# Power.net
KiCad netlist of a schematic drawn in Altium Designer
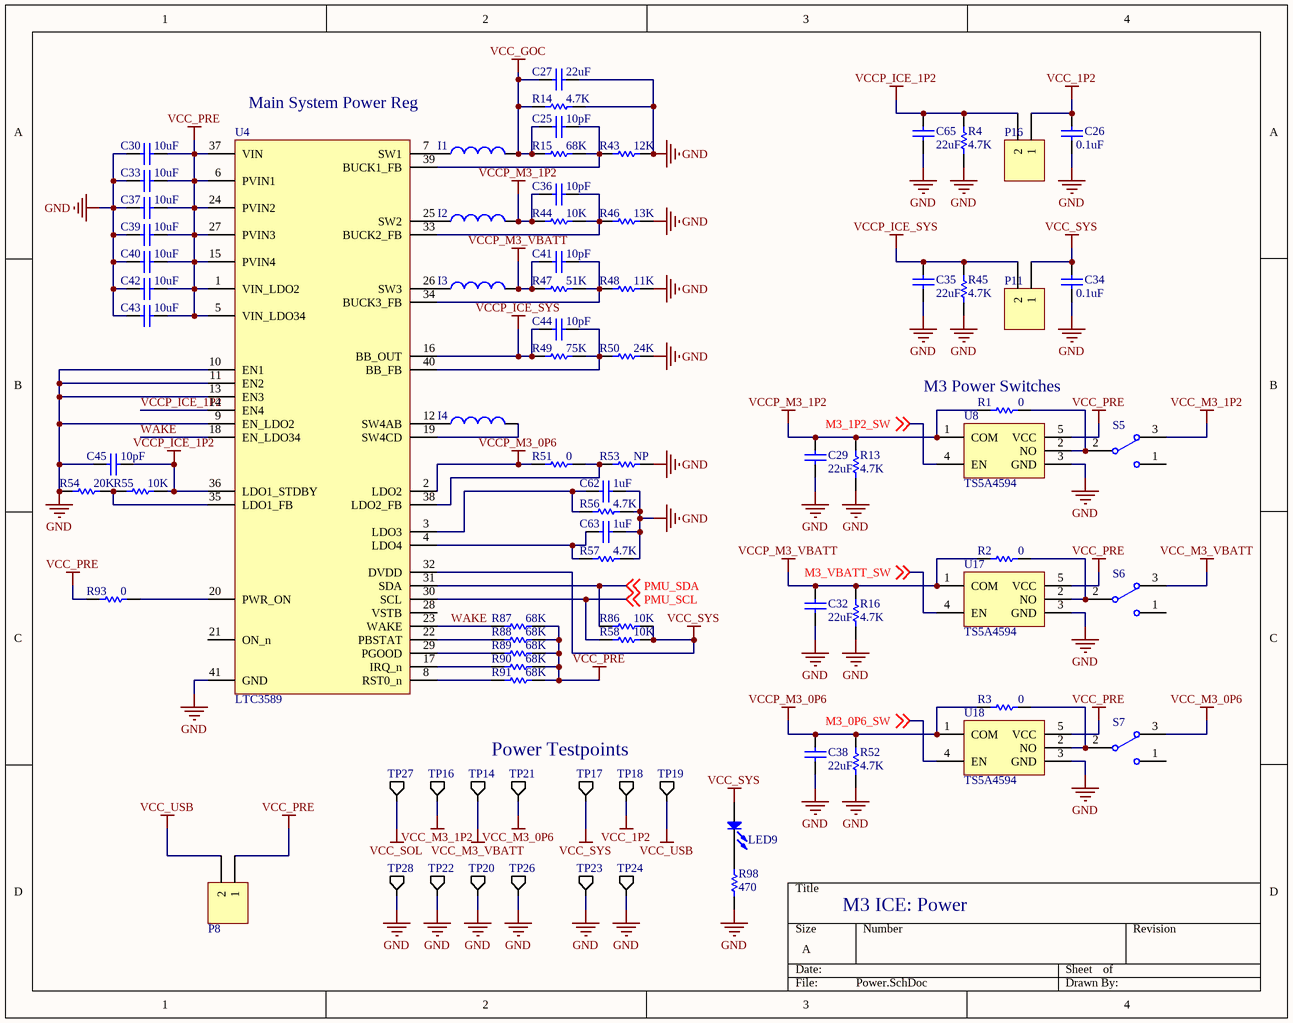
[diagram p0: Power.SchDoc]

(export (version "E")
  (design (tool "Eeschema 10.0.6"))
  (components
    (comp (ref "C25")
      (value "10pF")
      (footprint "0402")
      (description "Capacitor (Semiconductor SIM Model)")
      (fields
        (field (name "DISTPARTNO") "445-1235-1-ND")
        (field (name "MANPARTNO") "C1005C0G1H100D")
        (field (name "PUBLISHER") "Altium Limited")
      )
      (libsource (lib "Miscellaneous Devices") (part "Cap Semi"))
    )
    (comp (ref "C26")
      (value "0.1uF")
      (footprint "1608[0603]")
      (description "Capacitor (Semiconductor SIM Model)")
      (fields
        (field (name "DISTPARTNO") "445-1317-1-ND")
        (field (name "MANPARTNO") "C1608X7R1C104K")
        (field (name "PUBLISHER") "Altium Limited")
      )
      (libsource (lib "Miscellaneous Devices") (part "Cap Semi"))
    )
    (comp (ref "C27")
      (value "22uF")
      (footprint "0805")
      (description "Capacitor (Semiconductor SIM Model)")
      (fields
        (field (name "DISTPARTNO") "587-2782-1-ND")
        (field (name "MANPARTNO") "LMK316AB7226ML-TR")
        (field (name "PUBLISHER") "Altium Limited")
      )
      (libsource (lib "M3") (part "Cap Chip"))
    )
    (comp (ref "C29")
      (value "22uF")
      (footprint "0805")
      (description "Capacitor (Semiconductor SIM Model)")
      (fields
        (field (name "DISTPARTNO") "587-2782-1-ND")
        (field (name "MANPARTNO") "LMK316AB7226ML-TR")
        (field (name "PUBLISHER") "Altium Limited")
      )
      (libsource (lib "M3") (part "Cap Chip"))
    )
    (comp (ref "C30")
      (value "10uF")
      (footprint "0805")
      (description "Capacitor (Semiconductor SIM Model)")
      (fields
        (field (name "DISTPARTNO") "445-6857-1-ND")
        (field (name "MANPARTNO") "C2012X7R1A106K")
        (field (name "PUBLISHER") "Altium Limited")
      )
      (libsource (lib "M3") (part "Cap Chip"))
    )
    (comp (ref "C32")
      (value "22uF")
      (footprint "0805")
      (description "Capacitor (Semiconductor SIM Model)")
      (fields
        (field (name "DISTPARTNO") "587-2782-1-ND")
        (field (name "MANPARTNO") "LMK316AB7226ML-TR")
        (field (name "PUBLISHER") "Altium Limited")
      )
      (libsource (lib "M3") (part "Cap Chip"))
    )
    (comp (ref "C33")
      (value "10uF")
      (footprint "0805")
      (description "Capacitor (Semiconductor SIM Model)")
      (fields
        (field (name "DISTPARTNO") "445-6857-1-ND")
        (field (name "MANPARTNO") "C2012X7R1A106K")
        (field (name "PUBLISHER") "Altium Limited")
      )
      (libsource (lib "M3") (part "Cap Chip"))
    )
    (comp (ref "C34")
      (value "0.1uF")
      (footprint "1608[0603]")
      (description "Capacitor (Semiconductor SIM Model)")
      (fields
        (field (name "DISTPARTNO") "445-1317-1-ND")
        (field (name "MANPARTNO") "C1608X7R1C104K")
        (field (name "PUBLISHER") "Altium Limited")
      )
      (libsource (lib "Miscellaneous Devices") (part "Cap Semi"))
    )
    (comp (ref "C35")
      (value "22uF")
      (footprint "0805")
      (description "Capacitor (Semiconductor SIM Model)")
      (fields
        (field (name "DISTPARTNO") "587-2782-1-ND")
        (field (name "MANPARTNO") "LMK316AB7226ML-TR")
        (field (name "PUBLISHER") "Altium Limited")
      )
      (libsource (lib "M3") (part "Cap Chip"))
    )
    (comp (ref "C36")
      (value "10pF")
      (footprint "0402")
      (description "Capacitor (Semiconductor SIM Model)")
      (fields
        (field (name "DISTPARTNO") "445-1235-1-ND")
        (field (name "MANPARTNO") "C1005C0G1H100D")
        (field (name "PUBLISHER") "Altium Limited")
      )
      (libsource (lib "Miscellaneous Devices") (part "Cap Semi"))
    )
    (comp (ref "C37")
      (value "10uF")
      (footprint "0805")
      (description "Capacitor (Semiconductor SIM Model)")
      (fields
        (field (name "DISTPARTNO") "445-6857-1-ND")
        (field (name "MANPARTNO") "C2012X7R1A106K")
        (field (name "PUBLISHER") "Altium Limited")
      )
      (libsource (lib "M3") (part "Cap Chip"))
    )
    (comp (ref "C38")
      (value "22uF")
      (footprint "0805")
      (description "Capacitor (Semiconductor SIM Model)")
      (fields
        (field (name "DISTPARTNO") "587-2782-1-ND")
        (field (name "MANPARTNO") "LMK316AB7226ML-TR")
        (field (name "PUBLISHER") "Altium Limited")
      )
      (libsource (lib "M3") (part "Cap Chip"))
    )
    (comp (ref "C39")
      (value "10uF")
      (footprint "0805")
      (description "Capacitor (Semiconductor SIM Model)")
      (fields
        (field (name "DISTPARTNO") "445-6857-1-ND")
        (field (name "MANPARTNO") "C2012X7R1A106K")
        (field (name "PUBLISHER") "Altium Limited")
      )
      (libsource (lib "M3") (part "Cap Chip"))
    )
    (comp (ref "C40")
      (value "10uF")
      (footprint "0805")
      (description "Capacitor (Semiconductor SIM Model)")
      (fields
        (field (name "DISTPARTNO") "445-6857-1-ND")
        (field (name "MANPARTNO") "C2012X7R1A106K")
        (field (name "PUBLISHER") "Altium Limited")
      )
      (libsource (lib "M3") (part "Cap Chip"))
    )
    (comp (ref "C41")
      (value "10pF")
      (footprint "0402")
      (description "Capacitor (Semiconductor SIM Model)")
      (fields
        (field (name "DISTPARTNO") "445-1235-1-ND")
        (field (name "MANPARTNO") "C1005C0G1H100D")
        (field (name "PUBLISHER") "Altium Limited")
      )
      (libsource (lib "Miscellaneous Devices") (part "Cap Semi"))
    )
    (comp (ref "C42")
      (value "10uF")
      (footprint "0805")
      (description "Capacitor (Semiconductor SIM Model)")
      (fields
        (field (name "DISTPARTNO") "445-6857-1-ND")
        (field (name "MANPARTNO") "C2012X7R1A106K")
        (field (name "PUBLISHER") "Altium Limited")
      )
      (libsource (lib "M3") (part "Cap Chip"))
    )
    (comp (ref "C43")
      (value "10uF")
      (footprint "0805")
      (description "Capacitor (Semiconductor SIM Model)")
      (fields
        (field (name "DISTPARTNO") "445-6857-1-ND")
        (field (name "MANPARTNO") "C2012X7R1A106K")
        (field (name "PUBLISHER") "Altium Limited")
      )
      (libsource (lib "M3") (part "Cap Chip"))
    )
    (comp (ref "C44")
      (value "10pF")
      (footprint "0402")
      (description "Capacitor (Semiconductor SIM Model)")
      (fields
        (field (name "DISTPARTNO") "445-1235-1-ND")
        (field (name "MANPARTNO") "C1005C0G1H100D")
        (field (name "PUBLISHER") "Altium Limited")
      )
      (libsource (lib "Miscellaneous Devices") (part "Cap Semi"))
    )
    (comp (ref "C45")
      (value "10pF")
      (footprint "0402")
      (description "Capacitor (Semiconductor SIM Model)")
      (fields
        (field (name "DISTPARTNO") "445-1235-1-ND")
        (field (name "MANPARTNO") "C1005C0G1H100D")
        (field (name "PUBLISHER") "Altium Limited")
      )
      (libsource (lib "Miscellaneous Devices") (part "Cap Semi"))
    )
    (comp (ref "C62")
      (value "1uF")
      (footprint "0402")
      (description "Capacitor (Semiconductor SIM Model)")
      (fields
        (field (name "DISTPARTNO") "445-4991-1-ND")
        (field (name "MANPARTNO") "C1005X5R1A105M")
        (field (name "PUBLISHER") "Altium Limited")
      )
      (libsource (lib "Miscellaneous Devices") (part "Cap Semi"))
    )
    (comp (ref "C63")
      (value "1uF")
      (footprint "0402")
      (description "Capacitor (Semiconductor SIM Model)")
      (fields
        (field (name "DISTPARTNO") "445-4991-1-ND")
        (field (name "MANPARTNO") "C1005X5R1A105M")
        (field (name "PUBLISHER") "Altium Limited")
      )
      (libsource (lib "Miscellaneous Devices") (part "Cap Semi"))
    )
    (comp (ref "C65")
      (value "22uF")
      (footprint "0805")
      (description "Capacitor (Semiconductor SIM Model)")
      (fields
        (field (name "DISTPARTNO") "587-2782-1-ND")
        (field (name "MANPARTNO") "LMK316AB7226ML-TR")
        (field (name "PUBLISHER") "Altium Limited")
      )
      (libsource (lib "M3") (part "Cap Chip"))
    )
    (comp (ref "I1")
      (value "NR5040T1R5N")
      (footprint "INDUCTOR_.118x.142mm")
      (fields (field (name "DISTPARTNO") "541-1327-1-ND") (field (name "MANPARTNO") "IHLP1212AEER1R0M11"))
      (libsource (lib "M3") (part "IHLP1212"))
    )
    (comp (ref "I2")
      (value "NR5040T1R5N")
      (footprint "INDUCTOR_.118x.142mm")
      (fields (field (name "DISTPARTNO") "541-1327-1-ND") (field (name "MANPARTNO") "IHLP1212AEER1R0M11"))
      (libsource (lib "M3") (part "IHLP1212"))
    )
    (comp (ref "I3")
      (value "NR5040T1R5N")
      (footprint "INDUCTOR_.118x.142mm")
      (fields (field (name "DISTPARTNO") "541-1327-1-ND") (field (name "MANPARTNO") "IHLP1212AEER1R0M11"))
      (libsource (lib "M3") (part "IHLP1212"))
    )
    (comp (ref "I4")
      (value "NR5040T1R5N")
      (footprint "INDUCTOR_.118x.142mm")
      (fields (field (name "DISTPARTNO") "541-1327-1-ND") (field (name "MANPARTNO") "IHLP1212AEER1R0M11"))
      (libsource (lib "M3") (part "IHLP1212"))
    )
    (comp (ref "LED9")
      (value "LED 1206")
      (footprint "1206_LED")
      (fields (field (name "DISTPARTNO") "160-1169-1-ND") (field (name "MANPARTNO") "LTST-C150GKT"))
      (libsource (lib "M3") (part "LED 1206"))
    )
    (comp (ref "P8")
      (value "Header 2")
      (footprint "HDR1X2")
      (description "Header, 2-Pin")
      (fields (field (name "PUBLISHER") "Altium Limited"))
      (libsource (lib "Miscellaneous Connectors") (part "Header 2"))
    )
    (comp (ref "P11")
      (value "Header 2")
      (footprint "HDR1X2")
      (description "Header, 2-Pin")
      (fields (field (name "PUBLISHER") "Altium Limited"))
      (libsource (lib "Miscellaneous Connectors") (part "Header 2"))
    )
    (comp (ref "P16")
      (value "Header 2")
      (footprint "HDR1X2")
      (description "Header, 2-Pin")
      (fields (field (name "PUBLISHER") "Altium Limited"))
      (libsource (lib "Miscellaneous Connectors") (part "Header 2"))
    )
    (comp (ref "R1")
      (value "0")
      (footprint "0603")
      (description "Semiconductor Resistor")
      (fields
        (field (name "DISTPARTNO") "P0.0GCT-ND")
        (field (name "MANPARTNO") "ERJ-3GEY0R00V")
        (field (name "PUBLISHER") "Altium Limited")
      )
      (libsource (lib "M3") (part "Res Chip"))
    )
    (comp (ref "R2")
      (value "0")
      (footprint "0603")
      (description "Semiconductor Resistor")
      (fields
        (field (name "DISTPARTNO") "P0.0GCT-ND")
        (field (name "MANPARTNO") "ERJ-3GEY0R00V")
        (field (name "PUBLISHER") "Altium Limited")
      )
      (libsource (lib "M3") (part "Res Chip"))
    )
    (comp (ref "R3")
      (value "0")
      (footprint "0603")
      (description "Semiconductor Resistor")
      (fields
        (field (name "DISTPARTNO") "P0.0GCT-ND")
        (field (name "MANPARTNO") "ERJ-3GEY0R00V")
        (field (name "PUBLISHER") "Altium Limited")
      )
      (libsource (lib "M3") (part "Res Chip"))
    )
    (comp (ref "R4")
      (value "4.7K")
      (footprint "0603")
      (description "Semiconductor Resistor")
      (fields
        (field (name "DISTPARTNO") "P4.7KGCT-ND")
        (field (name "MANPARTNO") "ERJ-3GEYJ472V")
        (field (name "PUBLISHER") "Altium Limited")
      )
      (libsource (lib "M3") (part "Res Chip"))
    )
    (comp (ref "R13")
      (value "4.7K")
      (footprint "0603")
      (description "Semiconductor Resistor")
      (fields
        (field (name "DISTPARTNO") "P4.7KGCT-ND")
        (field (name "MANPARTNO") "ERJ-3GEYJ472V")
        (field (name "PUBLISHER") "Altium Limited")
      )
      (libsource (lib "M3") (part "Res Chip"))
    )
    (comp (ref "R14")
      (value "4.7K")
      (footprint "0603")
      (description "Semiconductor Resistor")
      (fields
        (field (name "DISTPARTNO") "P4.7KGCT-ND")
        (field (name "MANPARTNO") "ERJ-3GEYJ472V")
        (field (name "PUBLISHER") "Altium Limited")
      )
      (libsource (lib "M3") (part "Res Chip"))
    )
    (comp (ref "R15")
      (value "68K")
      (footprint "0402")
      (description "Semiconductor Resistor")
      (fields
        (field (name "DISTPARTNO") "P68.0KLCT-ND")
        (field (name "MANPARTNO") "ERJ-2RKF6802X")
        (field (name "PUBLISHER") "Altium Limited")
      )
      (libsource (lib "M3") (part "Res Chip"))
    )
    (comp (ref "R16")
      (value "4.7K")
      (footprint "0603")
      (description "Semiconductor Resistor")
      (fields
        (field (name "DISTPARTNO") "P4.7KGCT-ND")
        (field (name "MANPARTNO") "ERJ-3GEYJ472V")
        (field (name "PUBLISHER") "Altium Limited")
      )
      (libsource (lib "M3") (part "Res Chip"))
    )
    (comp (ref "R43")
      (value "12K")
      (footprint "0402")
      (description "Semiconductor Resistor")
      (fields
        (field (name "DISTPARTNO") "P12.0KLCT-ND")
        (field (name "MANPARTNO") "ERJ-2RKF1202X")
        (field (name "PUBLISHER") "Altium Limited")
      )
      (libsource (lib "M3") (part "Res Chip"))
    )
    (comp (ref "R44")
      (value "10K")
      (footprint "0402")
      (description "Semiconductor Resistor")
      (fields
        (field (name "DISTPARTNO") "P10.0KLCT-ND")
        (field (name "MANPARTNO") "ERJ-2RKF1002X")
        (field (name "PUBLISHER") "Altium Limited")
      )
      (libsource (lib "M3") (part "Res Chip"))
    )
    (comp (ref "R45")
      (value "4.7K")
      (footprint "0603")
      (description "Semiconductor Resistor")
      (fields
        (field (name "DISTPARTNO") "P4.7KGCT-ND")
        (field (name "MANPARTNO") "ERJ-3GEYJ472V")
        (field (name "PUBLISHER") "Altium Limited")
      )
      (libsource (lib "M3") (part "Res Chip"))
    )
    (comp (ref "R46")
      (value "13K")
      (footprint "0402")
      (description "Semiconductor Resistor")
      (fields
        (field (name "DISTPARTNO") "311-13.0KLRCT-ND")
        (field (name "MANPARTNO") "RC0402FR-0713KL")
        (field (name "PUBLISHER") "Altium Limited")
      )
      (libsource (lib "M3") (part "Res Chip"))
    )
    (comp (ref "R47")
      (value "51K")
      (footprint "0402")
      (description "Semiconductor Resistor")
      (fields
        (field (name "DISTPARTNO") "P51.0KLCT-ND")
        (field (name "MANPARTNO") "ERJ-2RKF5102X")
        (field (name "PUBLISHER") "Altium Limited")
      )
      (libsource (lib "M3") (part "Res Chip"))
    )
    (comp (ref "R48")
      (value "11K")
      (footprint "0402")
      (description "Semiconductor Resistor")
      (fields
        (field (name "DISTPARTNO") "P11.0KLCT-ND")
        (field (name "MANPARTNO") "ERJ-2RKF1102X")
        (field (name "PUBLISHER") "Altium Limited")
      )
      (libsource (lib "M3") (part "Res Chip"))
    )
    (comp (ref "R49")
      (value "75K")
      (footprint "0402")
      (description "Semiconductor Resistor")
      (fields
        (field (name "DISTPARTNO") "P75.0KLCT-ND")
        (field (name "MANPARTNO") "ERJ-2RKF7502X")
        (field (name "PUBLISHER") "Altium Limited")
      )
      (libsource (lib "M3") (part "Res Chip"))
    )
    (comp (ref "R50")
      (value "24K")
      (footprint "0402")
      (description "Semiconductor Resistor")
      (fields
        (field (name "DISTPARTNO") "RMCF0402FT24K0CT-ND")
        (field (name "MANPARTNO") "RMCF0402FT24K0")
        (field (name "PUBLISHER") "Altium Limited")
      )
      (libsource (lib "M3") (part "Res Chip"))
    )
    (comp (ref "R51")
      (value "0")
      (footprint "0402")
      (description "Semiconductor Resistor")
      (fields
        (field (name "DISTPARTNO") "P0.0JCT-ND")
        (field (name "MANPARTNO") "ERJ-2GE0R00X")
        (field (name "PUBLISHER") "Altium Limited")
      )
      (libsource (lib "M3") (part "Res Chip"))
    )
    (comp (ref "R52")
      (value "4.7K")
      (footprint "0603")
      (description "Semiconductor Resistor")
      (fields
        (field (name "DISTPARTNO") "P4.7KGCT-ND")
        (field (name "MANPARTNO") "ERJ-3GEYJ472V")
        (field (name "PUBLISHER") "Altium Limited")
      )
      (libsource (lib "M3") (part "Res Chip"))
    )
    (comp (ref "R53")
      (value "NP")
      (footprint "0402")
      (description "Semiconductor Resistor")
      (fields (field (name "Comment") "Res Chip") (field (name "PUBLISHER") "Altium Limited"))
      (libsource (lib "M3") (part "Res Chip"))
    )
    (comp (ref "R54")
      (value "20K")
      (footprint "0402")
      (description "Semiconductor Resistor")
      (fields
        (field (name "DISTPARTNO") "P20.0KLCT-ND")
        (field (name "MANPARTNO") "ERJ-2RKF2002X")
        (field (name "PUBLISHER") "Altium Limited")
      )
      (libsource (lib "M3") (part "Res Chip"))
    )
    (comp (ref "R55")
      (value "10K")
      (footprint "0402")
      (description "Semiconductor Resistor")
      (fields
        (field (name "DISTPARTNO") "P10.0KLCT-ND")
        (field (name "MANPARTNO") "ERJ-2RKF1002X")
        (field (name "PUBLISHER") "Altium Limited")
      )
      (libsource (lib "M3") (part "Res Chip"))
    )
    (comp (ref "R56")
      (value "4.7K")
      (footprint "0402")
      (description "Semiconductor Resistor")
      (fields
        (field (name "DISTPARTNO") "P4.70KLCT-ND")
        (field (name "MANPARTNO") "ERJ-2RKF4701X")
        (field (name "PUBLISHER") "Altium Limited")
      )
      (libsource (lib "M3") (part "Res Chip"))
    )
    (comp (ref "R57")
      (value "4.7K")
      (footprint "0402")
      (description "Semiconductor Resistor")
      (fields
        (field (name "DISTPARTNO") "P4.70KLCT-ND")
        (field (name "MANPARTNO") "ERJ-2RKF4701X")
        (field (name "PUBLISHER") "Altium Limited")
      )
      (libsource (lib "M3") (part "Res Chip"))
    )
    (comp (ref "R58")
      (value "10K")
      (footprint "0402")
      (description "Semiconductor Resistor")
      (fields
        (field (name "DISTPARTNO") "P10.0KLCT-ND")
        (field (name "MANPARTNO") "ERJ-2RKF1002X")
        (field (name "PUBLISHER") "Altium Limited")
      )
      (libsource (lib "M3") (part "Res Chip"))
    )
    (comp (ref "R86")
      (value "10K")
      (footprint "0402")
      (description "Semiconductor Resistor")
      (fields
        (field (name "DISTPARTNO") "P10.0KLCT-ND")
        (field (name "MANPARTNO") "ERJ-2RKF1002X")
        (field (name "PUBLISHER") "Altium Limited")
      )
      (libsource (lib "M3") (part "Res Chip"))
    )
    (comp (ref "R87")
      (value "68K")
      (footprint "0402")
      (description "Semiconductor Resistor")
      (fields
        (field (name "DISTPARTNO") "P68.0KLCT-ND")
        (field (name "MANPARTNO") "ERJ-2RKF6802X")
        (field (name "PUBLISHER") "Altium Limited")
      )
      (libsource (lib "M3") (part "Res Chip"))
    )
    (comp (ref "R88")
      (value "68K")
      (footprint "0402")
      (description "Semiconductor Resistor")
      (fields
        (field (name "DISTPARTNO") "P68.0KLCT-ND")
        (field (name "MANPARTNO") "ERJ-2RKF6802X")
        (field (name "PUBLISHER") "Altium Limited")
      )
      (libsource (lib "M3") (part "Res Chip"))
    )
    (comp (ref "R89")
      (value "68K")
      (footprint "0402")
      (description "Semiconductor Resistor")
      (fields
        (field (name "DISTPARTNO") "P68.0KLCT-ND")
        (field (name "MANPARTNO") "ERJ-2RKF6802X")
        (field (name "PUBLISHER") "Altium Limited")
      )
      (libsource (lib "M3") (part "Res Chip"))
    )
    (comp (ref "R90")
      (value "68K")
      (footprint "0402")
      (description "Semiconductor Resistor")
      (fields
        (field (name "DISTPARTNO") "P68.0KLCT-ND")
        (field (name "MANPARTNO") "ERJ-2RKF6802X")
        (field (name "PUBLISHER") "Altium Limited")
      )
      (libsource (lib "M3") (part "Res Chip"))
    )
    (comp (ref "R91")
      (value "68K")
      (footprint "0402")
      (description "Semiconductor Resistor")
      (fields
        (field (name "DISTPARTNO") "P68.0KLCT-ND")
        (field (name "MANPARTNO") "ERJ-2RKF6802X")
        (field (name "PUBLISHER") "Altium Limited")
      )
      (libsource (lib "M3") (part "Res Chip"))
    )
    (comp (ref "R93")
      (value "0")
      (footprint "0402")
      (description "Semiconductor Resistor")
      (fields
        (field (name "DISTPARTNO") "P0.0JCT-ND")
        (field (name "MANPARTNO") "ERJ-2GE0R00X")
        (field (name "PUBLISHER") "Altium Limited")
      )
      (libsource (lib "M3") (part "Res Chip"))
    )
    (comp (ref "R98")
      (value "470")
      (footprint "0603")
      (description "Semiconductor Resistor")
      (fields
        (field (name "DISTPARTNO") "P470GCT-ND")
        (field (name "MANPARTNO") "ERJ-3GEYJ471V")
        (field (name "PUBLISHER") "Altium Limited")
      )
      (libsource (lib "M3") (part "Res Chip"))
    )
    (comp (ref "S5")
      (value "OS102011MS2QN1")
      (footprint "SPDT_SW2")
      (description "SPDT Slide Switch")
      (fields (field (name "DISTPARTNO") "CKN9565-ND"))
      (libsource (lib "M3") (part "OS102011MS2QN1"))
    )
    (comp (ref "S6")
      (value "OS102011MS2QN1")
      (footprint "SPDT_SW2")
      (description "SPDT Slide Switch")
      (fields (field (name "DISTPARTNO") "CKN9565-ND"))
      (libsource (lib "M3") (part "OS102011MS2QN1"))
    )
    (comp (ref "S7")
      (value "OS102011MS2QN1")
      (footprint "SPDT_SW2")
      (description "SPDT Slide Switch")
      (fields (field (name "DISTPARTNO") "CKN9565-ND"))
      (libsource (lib "M3") (part "OS102011MS2QN1"))
    )
    (comp (ref "TP14") (value "TP") (footprint "TP") (libsource (lib "M3") (part "TP")))
    (comp (ref "TP16") (value "TP") (footprint "TP") (libsource (lib "M3") (part "TP")))
    (comp (ref "TP17") (value "TP") (footprint "TP") (libsource (lib "M3") (part "TP")))
    (comp (ref "TP18") (value "TP") (footprint "TP") (libsource (lib "M3") (part "TP")))
    (comp (ref "TP19") (value "TP") (footprint "TP") (libsource (lib "M3") (part "TP")))
    (comp (ref "TP20") (value "TP") (footprint "TP") (libsource (lib "M3") (part "TP")))
    (comp (ref "TP21") (value "TP") (footprint "TP") (libsource (lib "M3") (part "TP")))
    (comp (ref "TP22") (value "TP") (footprint "TP") (libsource (lib "M3") (part "TP")))
    (comp (ref "TP23") (value "TP") (footprint "TP") (libsource (lib "M3") (part "TP")))
    (comp (ref "TP24") (value "TP") (footprint "TP") (libsource (lib "M3") (part "TP")))
    (comp (ref "TP26") (value "TP") (footprint "TP") (libsource (lib "M3") (part "TP")))
    (comp (ref "TP27") (value "TP") (footprint "TP") (libsource (lib "M3") (part "TP")))
    (comp (ref "TP28") (value "TP") (footprint "TP") (libsource (lib "M3") (part "TP")))
    (comp (ref "U4")
      (value "LTC3589")
      (footprint "QFN-40")
      (fields (field (name "DISTPARTNO") "LTC3589EUJ-2#PBF-ND") (field (name "MANPARTNO") "LTC3589EUJ-2#PBF"))
      (libsource (lib "M3") (part "LTC3589"))
    )
    (comp (ref "U8")
      (value "TS5A4594")
      (footprint "SOT25")
      (description "SPST Analog Switch")
      (fields (field (name "DISTPARTNO") "296-17705-1-ND") (field (name "MANPARTNO") "TS5A4594DBVR"))
      (libsource (lib "M3") (part "TS5A4594"))
    )
    (comp (ref "U17")
      (value "TS5A4594")
      (footprint "SOT25")
      (description "SPST Analog Switch")
      (fields (field (name "DISTPARTNO") "296-17705-1-ND") (field (name "MANPARTNO") "TS5A4594DBVR"))
      (libsource (lib "M3") (part "TS5A4594"))
    )
    (comp (ref "U18")
      (value "TS5A4594")
      (footprint "SOT25")
      (description "SPST Analog Switch")
      (fields (field (name "DISTPARTNO") "296-17705-1-ND") (field (name "MANPARTNO") "TS5A4594DBVR"))
      (libsource (lib "M3") (part "TS5A4594"))
    )
  )
  (nets
    (net (code "1") (name "/WAKE") (class "Default")
      (node (ref "R87") (pin "1") (pinfunction "1_1") (pintype "passive"))
      (node (ref "U4") (pin "18") (pinfunction "EN_LDO34_18") (pintype "passive"))
      (node (ref "U4") (pin "23") (pinfunction "WAKE_23") (pintype "passive"))
    )
    (net (code "2") (name "GND") (class "Default")
      (node (ref "C26") (pin "1") (pinfunction "1_1") (pintype "passive"))
      (node (ref "C27") (pin "1") (pinfunction "1_1") (pintype "passive"))
      (node (ref "C29") (pin "1") (pinfunction "1_1") (pintype "passive"))
      (node (ref "C30") (pin "2") (pinfunction "2_2") (pintype "passive"))
      (node (ref "C32") (pin "1") (pinfunction "1_1") (pintype "passive"))
      (node (ref "C33") (pin "2") (pinfunction "2_2") (pintype "passive"))
      (node (ref "C34") (pin "1") (pinfunction "1_1") (pintype "passive"))
      (node (ref "C35") (pin "1") (pinfunction "1_1") (pintype "passive"))
      (node (ref "C37") (pin "2") (pinfunction "2_2") (pintype "passive"))
      (node (ref "C38") (pin "1") (pinfunction "1_1") (pintype "passive"))
      (node (ref "C39") (pin "2") (pinfunction "2_2") (pintype "passive"))
      (node (ref "C40") (pin "2") (pinfunction "2_2") (pintype "passive"))
      (node (ref "C42") (pin "2") (pinfunction "2_2") (pintype "passive"))
      (node (ref "C43") (pin "2") (pinfunction "2_2") (pintype "passive"))
      (node (ref "C45") (pin "2") (pinfunction "2_2") (pintype "passive"))
      (node (ref "C62") (pin "1") (pinfunction "1_1") (pintype "passive"))
      (node (ref "C63") (pin "1") (pinfunction "1_1") (pintype "passive"))
      (node (ref "C65") (pin "2") (pinfunction "2_2") (pintype "passive"))
      (node (ref "R13") (pin "1") (pinfunction "1_1") (pintype "passive"))
      (node (ref "R14") (pin "1") (pinfunction "1_1") (pintype "passive"))
      (node (ref "R16") (pin "1") (pinfunction "1_1") (pintype "passive"))
      (node (ref "R4") (pin "2") (pinfunction "2_2") (pintype "passive"))
      (node (ref "R43") (pin "2") (pinfunction "2_2") (pintype "passive"))
      (node (ref "R45") (pin "1") (pinfunction "1_1") (pintype "passive"))
      (node (ref "R46") (pin "2") (pinfunction "2_2") (pintype "passive"))
      (node (ref "R48") (pin "2") (pinfunction "2_2") (pintype "passive"))
      (node (ref "R50") (pin "2") (pinfunction "2_2") (pintype "passive"))
      (node (ref "R52") (pin "1") (pinfunction "1_1") (pintype "passive"))
      (node (ref "R53") (pin "2") (pinfunction "2_2") (pintype "passive"))
      (node (ref "R54") (pin "1") (pinfunction "1_1") (pintype "passive"))
      (node (ref "R56") (pin "2") (pinfunction "2_2") (pintype "passive"))
      (node (ref "R57") (pin "2") (pinfunction "2_2") (pintype "passive"))
      (node (ref "R98") (pin "1") (pinfunction "1_1") (pintype "passive"))
      (node (ref "TP20") (pin "1") (pinfunction "A_1") (pintype "passive"))
      (node (ref "TP22") (pin "1") (pinfunction "A_1") (pintype "passive"))
      (node (ref "TP23") (pin "1") (pinfunction "A_1") (pintype "passive"))
      (node (ref "TP24") (pin "1") (pinfunction "A_1") (pintype "passive"))
      (node (ref "TP26") (pin "1") (pinfunction "A_1") (pintype "passive"))
      (node (ref "TP28") (pin "1") (pinfunction "A_1") (pintype "passive"))
      (node (ref "U17") (pin "3") (pinfunction "GND_3") (pintype "passive"))
      (node (ref "U18") (pin "3") (pinfunction "GND_3") (pintype "passive"))
      (node (ref "U4") (pin "10") (pinfunction "EN1_10") (pintype "passive"))
      (node (ref "U4") (pin "11") (pinfunction "EN2_11") (pintype "passive"))
      (node (ref "U4") (pin "13") (pinfunction "EN3_13") (pintype "passive"))
      (node (ref "U4") (pin "41") (pinfunction "GND_41") (pintype "passive"))
      (node (ref "U4") (pin "9") (pinfunction "EN_LDO2_9") (pintype "passive"))
      (node (ref "U8") (pin "3") (pinfunction "GND_3") (pintype "passive"))
    )
    (net (code "3") (name "M3_0P6_SW") (class "Default")
      (node (ref "U18") (pin "4") (pinfunction "EN_4") (pintype "passive"))
    )
    (net (code "4") (name "M3_1P2_SW") (class "Default")
      (node (ref "U8") (pin "4") (pinfunction "EN_4") (pintype "passive"))
    )
    (net (code "5") (name "M3_VBATT_SW") (class "Default")
      (node (ref "U17") (pin "4") (pinfunction "EN_4") (pintype "passive"))
    )
    (net (code "6") (name "Net-(LED9-K)") (class "Default")
      (node (ref "LED9") (pin "2") (pinfunction "K_2") (pintype "passive"))
      (node (ref "R98") (pin "2") (pinfunction "2_2") (pintype "passive"))
    )
    (net (code "7") (name "Net-(U4-BB_FB)") (class "Default")
      (node (ref "C44") (pin "1") (pinfunction "1_1") (pintype "passive"))
      (node (ref "R49") (pin "2") (pinfunction "2_2") (pintype "passive"))
      (node (ref "R50") (pin "1") (pinfunction "1_1") (pintype "passive"))
      (node (ref "U4") (pin "40") (pinfunction "BB_FB_40") (pintype "passive"))
    )
    (net (code "8") (name "Net-(U4-BUCK1_FB)") (class "Default")
      (node (ref "C25") (pin "1") (pinfunction "1_1") (pintype "passive"))
      (node (ref "R15") (pin "2") (pinfunction "2_2") (pintype "passive"))
      (node (ref "R43") (pin "1") (pinfunction "1_1") (pintype "passive"))
      (node (ref "U4") (pin "39") (pinfunction "BUCK1_FB_39") (pintype "passive"))
    )
    (net (code "9") (name "Net-(U4-BUCK2_FB)") (class "Default")
      (node (ref "C36") (pin "1") (pinfunction "1_1") (pintype "passive"))
      (node (ref "R44") (pin "2") (pinfunction "2_2") (pintype "passive"))
      (node (ref "R46") (pin "1") (pinfunction "1_1") (pintype "passive"))
      (node (ref "U4") (pin "33") (pinfunction "BUCK2_FB_33") (pintype "passive"))
    )
    (net (code "10") (name "Net-(U4-BUCK3_FB)") (class "Default")
      (node (ref "C41") (pin "1") (pinfunction "1_1") (pintype "passive"))
      (node (ref "R47") (pin "2") (pinfunction "2_2") (pintype "passive"))
      (node (ref "R48") (pin "1") (pinfunction "1_1") (pintype "passive"))
      (node (ref "U4") (pin "34") (pinfunction "BUCK3_FB_34") (pintype "passive"))
    )
    (net (code "11") (name "Net-(U4-IRQ_n)") (class "Default")
      (node (ref "R90") (pin "1") (pinfunction "1_1") (pintype "passive"))
      (node (ref "U4") (pin "17") (pinfunction "IRQ_n_17") (pintype "passive"))
    )
    (net (code "12") (name "Net-(U4-LDO1_FB)") (class "Default")
      (node (ref "R54") (pin "2") (pinfunction "2_2") (pintype "passive"))
      (node (ref "R55") (pin "1") (pinfunction "1_1") (pintype "passive"))
      (node (ref "U4") (pin "35") (pinfunction "LDO1_FB_35") (pintype "passive"))
    )
    (net (code "13") (name "Net-(U4-LDO2_FB)") (class "Default")
      (node (ref "R51") (pin "2") (pinfunction "2_2") (pintype "passive"))
      (node (ref "R53") (pin "1") (pinfunction "1_1") (pintype "passive"))
      (node (ref "U4") (pin "38") (pinfunction "LDO2_FB_38") (pintype "passive"))
    )
    (net (code "14") (name "Net-(U4-LDO3)") (class "Default")
      (node (ref "C62") (pin "2") (pinfunction "2_2") (pintype "passive"))
      (node (ref "R56") (pin "1") (pinfunction "1_1") (pintype "passive"))
      (node (ref "U4") (pin "3") (pinfunction "LDO3_3") (pintype "passive"))
    )
    (net (code "15") (name "Net-(U4-LDO4)") (class "Default")
      (node (ref "C63") (pin "2") (pinfunction "2_2") (pintype "passive"))
      (node (ref "R57") (pin "1") (pinfunction "1_1") (pintype "passive"))
      (node (ref "U4") (pin "4") (pinfunction "LDO4_4") (pintype "passive"))
    )
    (net (code "16") (name "Net-(U4-PBSTAT)") (class "Default")
      (node (ref "R88") (pin "1") (pinfunction "1_1") (pintype "passive"))
      (node (ref "U4") (pin "22") (pinfunction "PBSTAT_22") (pintype "passive"))
    )
    (net (code "17") (name "Net-(U4-PGOOD)") (class "Default")
      (node (ref "R89") (pin "1") (pinfunction "1_1") (pintype "passive"))
      (node (ref "U4") (pin "29") (pinfunction "PGOOD_29") (pintype "passive"))
    )
    (net (code "18") (name "Net-(U4-PWR_ON)") (class "Default")
      (node (ref "R93") (pin "2") (pinfunction "2_2") (pintype "passive"))
      (node (ref "U4") (pin "20") (pinfunction "PWR_ON_20") (pintype "passive"))
    )
    (net (code "19") (name "Net-(U4-RST0_n)") (class "Default")
      (node (ref "R91") (pin "1") (pinfunction "1_1") (pintype "passive"))
      (node (ref "U4") (pin "8") (pinfunction "RST0_n_8") (pintype "passive"))
    )
    (net (code "20") (name "Net-(U4-SW1)") (class "Default")
      (node (ref "I1") (pin "1") (pinfunction "1_1") (pintype "passive"))
      (node (ref "U4") (pin "7") (pinfunction "SW1_7") (pintype "passive"))
    )
    (net (code "21") (name "Net-(U4-SW2)") (class "Default")
      (node (ref "I2") (pin "1") (pinfunction "1_1") (pintype "passive"))
      (node (ref "U4") (pin "25") (pinfunction "SW2_25") (pintype "passive"))
    )
    (net (code "22") (name "Net-(U4-SW3)") (class "Default")
      (node (ref "I3") (pin "1") (pinfunction "1_1") (pintype "passive"))
      (node (ref "U4") (pin "26") (pinfunction "SW3_26") (pintype "passive"))
    )
    (net (code "23") (name "Net-(U4-SW4AB)") (class "Default")
      (node (ref "I4") (pin "1") (pinfunction "1_1") (pintype "passive"))
      (node (ref "U4") (pin "12") (pinfunction "SW4AB_12") (pintype "passive"))
    )
    (net (code "24") (name "Net-(U4-SW4CD)") (class "Default")
      (node (ref "I4") (pin "2") (pinfunction "2_2") (pintype "passive"))
      (node (ref "U4") (pin "19") (pinfunction "SW4CD_19") (pintype "passive"))
    )
    (net (code "25") (name "Net-(U8-NO)") (class "Default")
      (node (ref "R1") (pin "1") (pinfunction "1_1") (pintype "passive"))
      (node (ref "S5") (pin "2") (pinfunction "2_2") (pintype "passive"))
      (node (ref "U8") (pin "2") (pinfunction "NO_2") (pintype "passive"))
    )
    (net (code "26") (name "Net-(U17-NO)") (class "Default")
      (node (ref "R2") (pin "1") (pinfunction "1_1") (pintype "passive"))
      (node (ref "S6") (pin "2") (pinfunction "2_2") (pintype "passive"))
      (node (ref "U17") (pin "2") (pinfunction "NO_2") (pintype "passive"))
    )
    (net (code "27") (name "Net-(U18-NO)") (class "Default")
      (node (ref "R3") (pin "1") (pinfunction "1_1") (pintype "passive"))
      (node (ref "S7") (pin "2") (pinfunction "2_2") (pintype "passive"))
      (node (ref "U18") (pin "2") (pinfunction "NO_2") (pintype "passive"))
    )
    (net (code "28") (name "PMU_SCL") (class "Default")
      (node (ref "R58") (pin "1") (pinfunction "1_1") (pintype "passive"))
      (node (ref "U4") (pin "30") (pinfunction "SCL_30") (pintype "passive"))
    )
    (net (code "29") (name "PMU_SDA") (class "Default")
      (node (ref "R86") (pin "1") (pinfunction "1_1") (pintype "passive"))
      (node (ref "U4") (pin "31") (pinfunction "SDA_31") (pintype "passive"))
    )
    (net (code "30") (name "VCCP_ICE_1P2") (class "Default")
      (node (ref "C45") (pin "1") (pinfunction "1_1") (pintype "passive"))
      (node (ref "C65") (pin "1") (pinfunction "1_1") (pintype "passive"))
      (node (ref "P16") (pin "2") (pinfunction "2_2") (pintype "passive"))
      (node (ref "R4") (pin "1") (pinfunction "1_1") (pintype "passive"))
      (node (ref "R55") (pin "2") (pinfunction "2_2") (pintype "passive"))
      (node (ref "U4") (pin "14") (pinfunction "EN4_14") (pintype "passive"))
      (node (ref "U4") (pin "36") (pinfunction "LDO1_STDBY_36") (pintype "passive"))
    )
    (net (code "31") (name "VCCP_ICE_SYS") (class "Default")
      (node (ref "C35") (pin "2") (pinfunction "2_2") (pintype "passive"))
      (node (ref "C44") (pin "2") (pinfunction "2_2") (pintype "passive"))
      (node (ref "P11") (pin "2") (pinfunction "2_2") (pintype "passive"))
      (node (ref "R45") (pin "2") (pinfunction "2_2") (pintype "passive"))
      (node (ref "R49") (pin "1") (pinfunction "1_1") (pintype "passive"))
      (node (ref "U4") (pin "16") (pinfunction "BB_OUT_16") (pintype "passive"))
    )
    (net (code "32") (name "VCCP_M3_0P6") (class "Default")
      (node (ref "C38") (pin "2") (pinfunction "2_2") (pintype "passive"))
      (node (ref "R3") (pin "2") (pinfunction "2_2") (pintype "passive"))
      (node (ref "R51") (pin "1") (pinfunction "1_1") (pintype "passive"))
      (node (ref "R52") (pin "2") (pinfunction "2_2") (pintype "passive"))
      (node (ref "U18") (pin "1") (pinfunction "COM_1") (pintype "passive"))
      (node (ref "U4") (pin "2") (pinfunction "LDO2_2") (pintype "passive"))
    )
    (net (code "33") (name "VCCP_M3_1P2") (class "Default")
      (node (ref "C29") (pin "2") (pinfunction "2_2") (pintype "passive"))
      (node (ref "C36") (pin "2") (pinfunction "2_2") (pintype "passive"))
      (node (ref "I2") (pin "2") (pinfunction "2_2") (pintype "passive"))
      (node (ref "R1") (pin "2") (pinfunction "2_2") (pintype "passive"))
      (node (ref "R13") (pin "2") (pinfunction "2_2") (pintype "passive"))
      (node (ref "R44") (pin "1") (pinfunction "1_1") (pintype "passive"))
      (node (ref "U8") (pin "1") (pinfunction "COM_1") (pintype "passive"))
    )
    (net (code "34") (name "VCCP_M3_VBATT") (class "Default")
      (node (ref "C32") (pin "2") (pinfunction "2_2") (pintype "passive"))
      (node (ref "C41") (pin "2") (pinfunction "2_2") (pintype "passive"))
      (node (ref "I3") (pin "2") (pinfunction "2_2") (pintype "passive"))
      (node (ref "R16") (pin "2") (pinfunction "2_2") (pintype "passive"))
      (node (ref "R2") (pin "2") (pinfunction "2_2") (pintype "passive"))
      (node (ref "R47") (pin "1") (pinfunction "1_1") (pintype "passive"))
      (node (ref "U17") (pin "1") (pinfunction "COM_1") (pintype "passive"))
    )
    (net (code "35") (name "VCC_1P2") (class "Default")
      (node (ref "C26") (pin "2") (pinfunction "2_2") (pintype "passive"))
      (node (ref "P16") (pin "1") (pinfunction "1_1") (pintype "passive"))
      (node (ref "TP18") (pin "1") (pinfunction "A_1") (pintype "passive"))
    )
    (net (code "36") (name "VCC_GOC") (class "Default")
      (node (ref "C25") (pin "2") (pinfunction "2_2") (pintype "passive"))
      (node (ref "C27") (pin "2") (pinfunction "2_2") (pintype "passive"))
      (node (ref "I1") (pin "2") (pinfunction "2_2") (pintype "passive"))
      (node (ref "R14") (pin "2") (pinfunction "2_2") (pintype "passive"))
      (node (ref "R15") (pin "1") (pinfunction "1_1") (pintype "passive"))
    )
    (net (code "37") (name "VCC_M3_0P6") (class "Default")
      (node (ref "S7") (pin "3") (pinfunction "3_3") (pintype "passive"))
      (node (ref "TP21") (pin "1") (pinfunction "A_1") (pintype "passive"))
    )
    (net (code "38") (name "VCC_M3_1P2") (class "Default")
      (node (ref "S5") (pin "3") (pinfunction "3_3") (pintype "passive"))
      (node (ref "TP16") (pin "1") (pinfunction "A_1") (pintype "passive"))
    )
    (net (code "39") (name "VCC_M3_VBATT") (class "Default")
      (node (ref "S6") (pin "3") (pinfunction "3_3") (pintype "passive"))
      (node (ref "TP14") (pin "1") (pinfunction "A_1") (pintype "passive"))
    )
    (net (code "40") (name "VCC_PRE") (class "Default")
      (node (ref "C30") (pin "1") (pinfunction "1_1") (pintype "passive"))
      (node (ref "C33") (pin "1") (pinfunction "1_1") (pintype "passive"))
      (node (ref "C37") (pin "1") (pinfunction "1_1") (pintype "passive"))
      (node (ref "C39") (pin "1") (pinfunction "1_1") (pintype "passive"))
      (node (ref "C40") (pin "1") (pinfunction "1_1") (pintype "passive"))
      (node (ref "C42") (pin "1") (pinfunction "1_1") (pintype "passive"))
      (node (ref "C43") (pin "1") (pinfunction "1_1") (pintype "passive"))
      (node (ref "P8") (pin "1") (pinfunction "1_1") (pintype "passive"))
      (node (ref "R87") (pin "2") (pinfunction "2_2") (pintype "passive"))
      (node (ref "R88") (pin "2") (pinfunction "2_2") (pintype "passive"))
      (node (ref "R89") (pin "2") (pinfunction "2_2") (pintype "passive"))
      (node (ref "R90") (pin "2") (pinfunction "2_2") (pintype "passive"))
      (node (ref "R91") (pin "2") (pinfunction "2_2") (pintype "passive"))
      (node (ref "R93") (pin "1") (pinfunction "1_1") (pintype "passive"))
      (node (ref "U17") (pin "5") (pinfunction "VCC_5") (pintype "passive"))
      (node (ref "U18") (pin "5") (pinfunction "VCC_5") (pintype "passive"))
      (node (ref "U4") (pin "1") (pinfunction "VIN_LDO2_1") (pintype "passive"))
      (node (ref "U4") (pin "15") (pinfunction "PVIN4_15") (pintype "passive"))
      (node (ref "U4") (pin "24") (pinfunction "PVIN2_24") (pintype "passive"))
      (node (ref "U4") (pin "27") (pinfunction "PVIN3_27") (pintype "passive"))
      (node (ref "U4") (pin "37") (pinfunction "VIN_37") (pintype "passive"))
      (node (ref "U4") (pin "5") (pinfunction "VIN_LDO34_5") (pintype "passive"))
      (node (ref "U4") (pin "6") (pinfunction "PVIN1_6") (pintype "passive"))
      (node (ref "U8") (pin "5") (pinfunction "VCC_5") (pintype "passive"))
    )
    (net (code "41") (name "VCC_SOL") (class "Default")
      (node (ref "TP27") (pin "1") (pinfunction "A_1") (pintype "passive"))
    )
    (net (code "42") (name "VCC_SYS") (class "Default")
      (node (ref "C34") (pin "2") (pinfunction "2_2") (pintype "passive"))
      (node (ref "LED9") (pin "1") (pinfunction "A_1") (pintype "passive"))
      (node (ref "P11") (pin "1") (pinfunction "1_1") (pintype "passive"))
      (node (ref "R58") (pin "2") (pinfunction "2_2") (pintype "passive"))
      (node (ref "R86") (pin "2") (pinfunction "2_2") (pintype "passive"))
      (node (ref "TP17") (pin "1") (pinfunction "A_1") (pintype "passive"))
      (node (ref "U4") (pin "32") (pinfunction "DVDD_32") (pintype "passive"))
    )
    (net (code "43") (name "VCC_USB") (class "Default")
      (node (ref "P8") (pin "2") (pinfunction "2_2") (pintype "passive"))
      (node (ref "TP19") (pin "1") (pinfunction "A_1") (pintype "passive"))
    )
    (net (code "44") (name "unconnected-(S5-Pad1)") (class "Default")
      (node (ref "S5") (pin "1") (pinfunction "1_1") (pintype "passive"))
    )
    (net (code "45") (name "unconnected-(S6-Pad1)") (class "Default")
      (node (ref "S6") (pin "1") (pinfunction "1_1") (pintype "passive"))
    )
    (net (code "46") (name "unconnected-(S7-Pad1)") (class "Default")
      (node (ref "S7") (pin "1") (pinfunction "1_1") (pintype "passive"))
    )
    (net (code "47") (name "unconnected-(U4-ON_n-Pad21)") (class "Default")
      (node (ref "U4") (pin "21") (pinfunction "ON_n_21") (pintype "passive"))
    )
    (net (code "48") (name "unconnected-(U4-VSTB-Pad28)") (class "Default")
      (node (ref "U4") (pin "28") (pinfunction "VSTB_28") (pintype "passive"))
    )
  )
)
